# 780-00012-P4_rev3_Sch_M2_Focus_Drive.net
KiCad netlist of a schematic drawn in Altium Designer
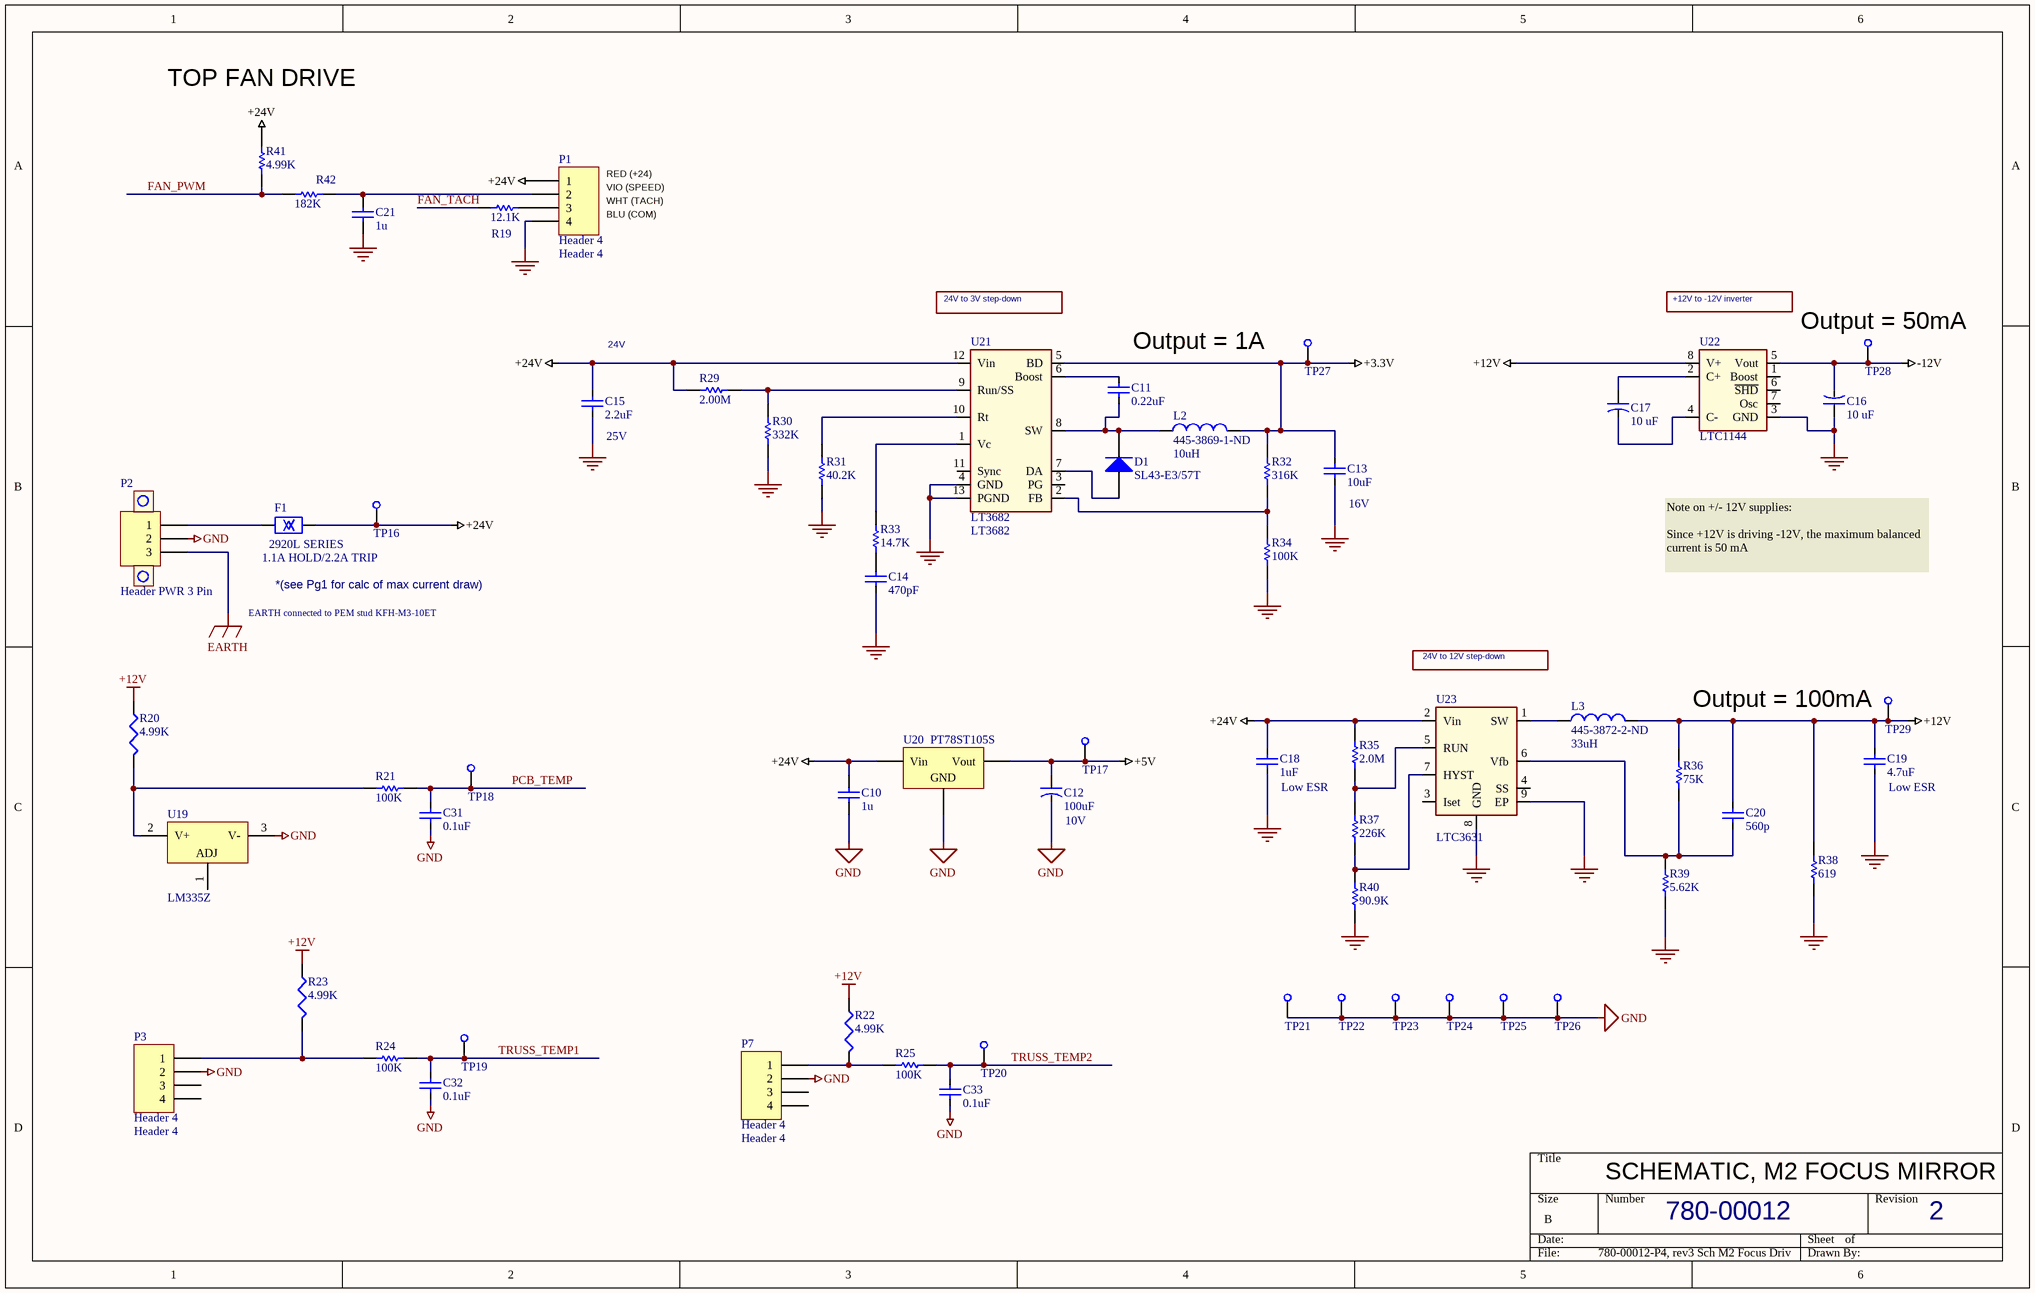
[diagram p0: 780-00012-P4, rev3 Sch M2 Focus Drive.SchDoc]

(export (version "E")
  (design (tool "Eeschema 10.0.6"))
  (components
    (comp (ref "C10")
      (value "1u")
      (footprint "2012[0805]")
      (description "Capacitor")
      (fields (field (name "MANUFACTURER") "Taiyo Yuden"))
      (libsource (lib "Miscellaneous Devices") (part "Cap"))
    )
    (comp (ref "C11")
      (value "0.22uF")
      (footprint "SMD_0805")
      (description "Capacitor")
      (fields (field (name "Comment") "Cap SMD"))
      (libsource (lib "Richs Schematic Components") (part "Cap SMD"))
    )
    (comp (ref "C12")
      (value "10V")
      (footprint "SMD_CAP_7343")
      (description "outline 6.0mm x 3.2mm")
      (fields (field (name "MANUFACTURER") "kEMET") (field (name "ALTIUM_VALUE") "100uF"))
      (libsource (lib "Richs Schematic Components") (part "Cap Tant 35V"))
    )
    (comp (ref "C13")
      (value "16V")
      (footprint "SMD_0805")
      (description "Capacitor")
      (fields (field (name "ALTIUM_VALUE") "10uF"))
      (libsource (lib "Richs Schematic Components") (part "Cap SMD"))
    )
    (comp (ref "C14")
      (value "470pF")
      (footprint "SMD_0805")
      (description "Capacitor")
      (fields (field (name "Comment") "Cap SMD"))
      (libsource (lib "Richs Schematic Components") (part "Cap SMD"))
    )
    (comp (ref "C15")
      (value "25V")
      (footprint "SMD_0805")
      (description "Capacitor")
      (fields (field (name "MANUFACTURER") "Taiyo Yuden") (field (name "ALTIUM_VALUE") "2.2uF"))
      (libsource (lib "Richs Schematic Components") (part "Cap SMD"))
    )
    (comp (ref "C16")
      (value "10 uF")
      (footprint "SMD_CAP_3216")
      (description "outline 3.2mm x 1.6mm")
      (fields (field (name "MANUFACTURER") "KEMET") (field (name "Comment") "16V"))
      (libsource (lib "Richs Schematic Components") (part "Cap Tant 16V"))
    )
    (comp (ref "C17")
      (value "10 uF")
      (footprint "SMD_CAP_3216")
      (description "outline 3.2mm x 1.6mm")
      (fields (field (name "MANUFACTURER") "KEMET") (field (name "Comment") "16V"))
      (libsource (lib "Richs Schematic Components") (part "Cap Tant 16V"))
    )
    (comp (ref "C18")
      (value "Low ESR")
      (footprint "SMD_1206")
      (description "Capacitor")
      (fields (field (name "MANUFACTURER") "TDK") (field (name "ALTIUM_VALUE") "1uF"))
      (libsource (lib "Richs Schematic Components") (part "Cap SMD"))
    )
    (comp (ref "C19")
      (value "Low ESR")
      (footprint "SMD_1206")
      (description "Capacitor")
      (fields (field (name "MANUFACTURER") "TDK") (field (name "ALTIUM_VALUE") "4.7uF"))
      (libsource (lib "Richs Schematic Components") (part "Cap SMD"))
    )
    (comp (ref "C20")
      (value "560p")
      (footprint "SMD_0805")
      (description "Capacitor")
      (fields (field (name "Comment") "Cap SMD"))
      (libsource (lib "Richs Schematic Components") (part "Cap SMD"))
    )
    (comp (ref "C21")
      (value "1u")
      (footprint "2012[0805]")
      (description "Capacitor")
      (fields (field (name "MANUFACTURER") "Taiyo Yuden"))
      (libsource (lib "Miscellaneous Devices") (part "Cap"))
    )
    (comp (ref "C31")
      (value "0.1uF")
      (footprint "SMD_0805")
      (description "Capacitor")
      (fields (field (name "MANUFACTURER") "AVX") (field (name "Comment") "Cap SMD"))
      (libsource (lib "Richs Schematic Components") (part "Cap SMD"))
    )
    (comp (ref "C32")
      (value "0.1uF")
      (footprint "SMD_0805")
      (description "Capacitor")
      (fields (field (name "MANUFACTURER") "AVX") (field (name "Comment") "Cap SMD"))
      (libsource (lib "Richs Schematic Components") (part "Cap SMD"))
    )
    (comp (ref "C33")
      (value "0.1uF")
      (footprint "SMD_0805")
      (description "Capacitor")
      (fields (field (name "MANUFACTURER") "AVX") (field (name "Comment") "Cap SMD"))
      (libsource (lib "Richs Schematic Components") (part "Cap SMD"))
    )
    (comp (ref "D1")
      (value "SL43-E3/57T")
      (footprint "DO-214AB")
      (description "Default Diode")
      (fields (field (name "MANUFACTURER") "Vishay/Dale"))
      (libsource (lib "Miscellaneous Devices") (part "Diode"))
    )
    (comp (ref "F1")
      (value "2920L SERIES")
      (footprint "SMD 2920  PolySwitch")
      (description "Polyswitch")
      (fields (field (name "ALTIUM_VALUE") "1.1A HOLD/2.2A TRIP"))
      (libsource (lib "Richs Schematic Components") (part "Fuse Resettable"))
    )
    (comp (ref "L2")
      (value "445-3869-1-ND")
      (footprint "Inductor TDC SLF")
      (description "Inductor")
      (fields (field (name "MANUFACTURER") "TDK") (field (name "ALTIUM_VALUE") "10uH"))
      (libsource (lib "Richs Schematic Components") (part "Inductor SMD 10uH 1.8A"))
    )
    (comp (ref "L3")
      (value "445-3872-2-ND")
      (footprint "Inductor TDC SLF")
      (description "Inductor")
      (fields (field (name "MANUFACTURER") "TDK") (field (name "ALTIUM_VALUE") "33uH"))
      (libsource (lib "Richs Schematic Components") (part "Inductor SMD 10uH 1.8A"))
    )
    (comp (ref "P1")
      (value "Header 4")
      (footprint "HDR1X4 for IDC")
      (description "Header, 4-Pin")
      (fields (field (name "ALTIUM_VALUE") "Header 4"))
      (libsource (lib "") (part "Header 4_1"))
    )
    (comp (ref "P2")
      (value "Header PWR 3 Pin")
      (footprint "HDR-3 pin w/screw")
      (description "Header, 3-Pin")
      (fields (field (name "MANUFACTURER") "Tyco"))
      (libsource (lib "Richs Schematic Components") (part "Header 3 PWR"))
    )
    (comp (ref "P3")
      (value "Header 4")
      (footprint "HDR1X4 for IDC")
      (description "Header, 4-Pin")
      (fields (field (name "ALTIUM_VALUE") "Header 4"))
      (libsource (lib "Richs Schematic Components") (part "Header 4"))
    )
    (comp (ref "P7")
      (value "Header 4")
      (footprint "HDR1X4 for IDC")
      (description "Header, 4-Pin")
      (fields (field (name "ALTIUM_VALUE") "Header 4"))
      (libsource (lib "Richs Schematic Components") (part "Header 4"))
    )
    (comp (ref "R19")
      (value "12.1K")
      (footprint "SMD_0805")
      (description "Resistor 0805")
      (fields (field (name "MANUFACTURER") "Vishay/Dale") (field (name "Comment") "Res 0805"))
      (libsource (lib "Richs Schematic Components") (part "Res SMD"))
    )
    (comp (ref "R20")
      (value "4.99K")
      (footprint "smd_0805")
      (description "Resistor")
      (fields (field (name "MANUFACTURER") "DALE") (field (name "Comment") "Res3"))
      (libsource (lib "Miscellaneous Devices") (part "Res3"))
    )
    (comp (ref "R21")
      (value "100K")
      (footprint "SMD_0805")
      (description "Resistor")
      (fields (field (name "MANUFACTURER") "Vishay/Dale") (field (name "Comment") "Res SMD"))
      (libsource (lib "Richs Schematic Components") (part "Res SMD"))
    )
    (comp (ref "R22")
      (value "4.99K")
      (footprint "smd_0805")
      (description "Resistor")
      (fields (field (name "MANUFACTURER") "DALE") (field (name "Comment") "Res3"))
      (libsource (lib "Miscellaneous Devices") (part "Res3"))
    )
    (comp (ref "R23")
      (value "4.99K")
      (footprint "smd_0805")
      (description "Resistor")
      (fields (field (name "MANUFACTURER") "DALE") (field (name "Comment") "Res3"))
      (libsource (lib "Miscellaneous Devices") (part "Res3"))
    )
    (comp (ref "R24")
      (value "100K")
      (footprint "SMD_0805")
      (description "Resistor")
      (fields (field (name "MANUFACTURER") "Vishay/Dale") (field (name "Comment") "Res SMD"))
      (libsource (lib "Richs Schematic Components") (part "Res SMD"))
    )
    (comp (ref "R25")
      (value "100K")
      (footprint "SMD_0805")
      (description "Resistor")
      (fields (field (name "MANUFACTURER") "Vishay/Dale") (field (name "Comment") "Res SMD"))
      (libsource (lib "Richs Schematic Components") (part "Res SMD"))
    )
    (comp (ref "R29")
      (value "2.00M")
      (footprint "SMD_0805")
      (description "Resistor 0805")
      (fields (field (name "MANUFACTURER") "Vishay/Dale") (field (name "Comment") "Res 0805"))
      (libsource (lib "Richs Schematic Components") (part "Res SMD"))
    )
    (comp (ref "R30")
      (value "332K")
      (footprint "SMD_0805")
      (description "Resistor 0805")
      (fields (field (name "MANUFACTURER") "Vishay/Dale") (field (name "Comment") "Res 0805"))
      (libsource (lib "Richs Schematic Components") (part "Res SMD"))
    )
    (comp (ref "R31")
      (value "40.2K")
      (footprint "SMD_0805")
      (description "Resistor 0805")
      (fields (field (name "MANUFACTURER") "Vishay/Dale") (field (name "Comment") "Res 0805"))
      (libsource (lib "Richs Schematic Components") (part "Res SMD"))
    )
    (comp (ref "R32")
      (value "316K")
      (footprint "SMD_0805")
      (description "Resistor 0805")
      (fields (field (name "MANUFACTURER") "Vishay/Dale") (field (name "Comment") "Res 0805"))
      (libsource (lib "Richs Schematic Components") (part "Res SMD"))
    )
    (comp (ref "R33")
      (value "14.7K")
      (footprint "SMD_0805")
      (description "Resistor 0805")
      (fields (field (name "MANUFACTURER") "Vishay/Dale") (field (name "Comment") "Res 0805"))
      (libsource (lib "Richs Schematic Components") (part "Res SMD"))
    )
    (comp (ref "R34")
      (value "100K")
      (footprint "SMD_0805")
      (description "Resistor 0805")
      (fields (field (name "MANUFACTURER") "Vishay/Dale") (field (name "Comment") "Res 0805"))
      (libsource (lib "Richs Schematic Components") (part "Res SMD"))
    )
    (comp (ref "R35")
      (value "2.0M")
      (footprint "SMD_0805")
      (description "Resistor 0805")
      (fields (field (name "MANUFACTURER") "Vishay/Dale") (field (name "Comment") "Res 0805"))
      (libsource (lib "Richs Schematic Components") (part "Res SMD"))
    )
    (comp (ref "R36")
      (value "75K")
      (footprint "SMD_0805")
      (description "Resistor 0805")
      (fields (field (name "MANUFACTURER") "Vishay/Dale") (field (name "Comment") "Res 0805"))
      (libsource (lib "Richs Schematic Components") (part "Res SMD"))
    )
    (comp (ref "R37")
      (value "226K")
      (footprint "SMD_0805")
      (description "Resistor 0805")
      (fields (field (name "MANUFACTURER") "Vishay/Dale") (field (name "Comment") "Res 0805"))
      (libsource (lib "Richs Schematic Components") (part "Res SMD"))
    )
    (comp (ref "R38")
      (value "619")
      (footprint "SMD_0805")
      (description "Resistor 0805")
      (fields (field (name "MANUFACTURER") "Vishay/Dale") (field (name "Comment") "Res 0805"))
      (libsource (lib "Richs Schematic Components") (part "Res SMD"))
    )
    (comp (ref "R39")
      (value "5.62K")
      (footprint "SMD_0805")
      (description "Resistor 0805")
      (fields (field (name "MANUFACTURER") "Vishay/Dale") (field (name "Comment") "Res 0805"))
      (libsource (lib "Richs Schematic Components") (part "Res SMD"))
    )
    (comp (ref "R40")
      (value "90.9K")
      (footprint "SMD_0805")
      (description "Resistor 0805")
      (fields (field (name "MANUFACTURER") "Vishay/Dale") (field (name "Comment") "Res 0805"))
      (libsource (lib "Richs Schematic Components") (part "Res SMD"))
    )
    (comp (ref "R41")
      (value "4.99K")
      (footprint "SMD_0805")
      (description "Resistor 0805")
      (fields (field (name "MANUFACTURER") "Vishay/Dale") (field (name "Comment") "Res 0805"))
      (libsource (lib "Richs Schematic Components") (part "Res SMD"))
    )
    (comp (ref "R42")
      (value "182K")
      (footprint "SMD_0805")
      (description "Resistor 0805")
      (fields (field (name "MANUFACTURER") "Vishay/Dale") (field (name "Comment") "Res 0805"))
      (libsource (lib "Richs Schematic Components") (part "Res SMD"))
    )
    (comp (ref "TP16")
      (value "Test Point SMD")
      (footprint "SMD_TEST POINT")
      (description "SMD loop test point")
      (libsource (lib "Richs Schematic Components") (part "Test Point SMD"))
    )
    (comp (ref "TP17")
      (value "Test Point SMD")
      (footprint "SMD_TEST POINT")
      (description "SMD loop test point")
      (libsource (lib "Richs Schematic Components") (part "Test Point SMD"))
    )
    (comp (ref "TP18")
      (value "Test Point SMD")
      (footprint "SMD_TEST POINT")
      (description "SMD loop test point")
      (libsource (lib "Richs Schematic Components") (part "Test Point SMD"))
    )
    (comp (ref "TP19")
      (value "Test Point SMD")
      (footprint "SMD_TEST POINT")
      (description "SMD loop test point")
      (libsource (lib "Richs Schematic Components") (part "Test Point SMD"))
    )
    (comp (ref "TP20")
      (value "Test Point SMD")
      (footprint "SMD_TEST POINT")
      (description "SMD loop test point")
      (libsource (lib "Richs Schematic Components") (part "Test Point SMD"))
    )
    (comp (ref "TP21")
      (value "Test Point SMD")
      (footprint "SMD_TEST POINT")
      (description "SMD loop test point")
      (libsource (lib "Richs Schematic Components") (part "Test Point SMD"))
    )
    (comp (ref "TP22")
      (value "Test Point SMD")
      (footprint "SMD_TEST POINT")
      (description "SMD loop test point")
      (libsource (lib "Richs Schematic Components") (part "Test Point SMD"))
    )
    (comp (ref "TP23")
      (value "Test Point SMD")
      (footprint "SMD_TEST POINT")
      (description "SMD loop test point")
      (libsource (lib "Richs Schematic Components") (part "Test Point SMD"))
    )
    (comp (ref "TP24")
      (value "Test Point SMD")
      (footprint "SMD_TEST POINT")
      (description "SMD loop test point")
      (libsource (lib "Richs Schematic Components") (part "Test Point SMD"))
    )
    (comp (ref "TP25")
      (value "Test Point SMD")
      (footprint "SMD_TEST POINT")
      (description "SMD loop test point")
      (libsource (lib "Richs Schematic Components") (part "Test Point SMD"))
    )
    (comp (ref "TP26")
      (value "Test Point SMD")
      (footprint "SMD_TEST POINT")
      (description "SMD loop test point")
      (libsource (lib "Richs Schematic Components") (part "Test Point SMD"))
    )
    (comp (ref "TP27")
      (value "Test Point SMD")
      (footprint "SMD_TEST POINT")
      (description "SMD loop test point")
      (libsource (lib "Richs Schematic Components") (part "Test Point SMD"))
    )
    (comp (ref "TP28")
      (value "Test Point SMD")
      (footprint "SMD_TEST POINT")
      (description "SMD loop test point")
      (libsource (lib "Richs Schematic Components") (part "Test Point SMD"))
    )
    (comp (ref "TP29")
      (value "Test Point SMD")
      (footprint "SMD_TEST POINT")
      (description "SMD loop test point")
      (libsource (lib "Richs Schematic Components") (part "Test Point SMD"))
    )
    (comp (ref "U19")
      (value "LM335Z")
      (footprint "Z03A")
      (description "Precision Temperature Sensor")
      (fields (field (name "MANUFACTURER") "National Semiconductor"))
      (libsource (lib "NSC Temperature Sensor") (part "LM335Z"))
    )
    (comp (ref "U20")
      (value "PT78ST105S")
      (footprint "PSIP_3_SMD")
      (description "Voltage Regulator")
      (fields (field (name "MANUFACTURER") "Texas Instruments"))
      (libsource (lib "Miscellaneous Devices") (part "Volt Reg"))
    )
    (comp (ref "U21")
      (value "LT3682")
      (footprint "DD12/DFN12")
      (description "1A uPwr Step-Down switching regulator")
      (fields (field (name "MANUFACTURER") "Linear") (field (name "ALTIUM_VALUE") "LT3682"))
      (libsource (lib "Richs Schematic Components") (part "LT3682"))
    )
    (comp (ref "U22")
      (value "LTC1144")
      (footprint "S8_M")
      (description "IC VOLT CONV SW-CAP W/SHTDN8SOIC")
      (fields (field (name "MANUFACTURER") "Linear"))
      (libsource (lib "Richs Schematic Components") (part "LTC1144"))
    )
    (comp (ref "U23")
      (value "LTC3631")
      (footprint "DD8/DFN8")
      (description "IC CONV STP-DWN ADJ 8-DFN")
      (fields (field (name "MANUFACTURER") "Linear"))
      (libsource (lib "Richs Schematic Components") (part "LTC3631"))
    )
  )
  (nets
    (net (code "1") (name "+3.3V") (class "Default")
      (node (ref "C13") (pin "2") (pinfunction "2_2") (pintype "passive"))
      (node (ref "L2") (pin "2") (pinfunction "2_2") (pintype "passive"))
      (node (ref "R32") (pin "2") (pinfunction "2_2") (pintype "passive"))
      (node (ref "TP27") (pin "1") (pinfunction "TP_1") (pintype "passive"))
      (node (ref "U21") (pin "5") (pinfunction "BD_5") (pintype "passive"))
    )
    (net (code "2") (name "+5V") (class "Default")
      (node (ref "C12") (pin "pos") (pinfunction "1_pos") (pintype "passive"))
      (node (ref "TP17") (pin "1") (pinfunction "TP_1") (pintype "passive"))
      (node (ref "U20") (pin "3") (pinfunction "Vout_3") (pintype "passive"))
    )
    (net (code "3") (name "+12V") (class "Default")
      (node (ref "C19") (pin "2") (pinfunction "2_2") (pintype "passive"))
      (node (ref "C20") (pin "2") (pinfunction "2_2") (pintype "passive"))
      (node (ref "L3") (pin "2") (pinfunction "2_2") (pintype "passive"))
      (node (ref "R20") (pin "1") (pinfunction "1_1") (pintype "passive"))
      (node (ref "R22") (pin "1") (pinfunction "1_1") (pintype "passive"))
      (node (ref "R23") (pin "1") (pinfunction "1_1") (pintype "passive"))
      (node (ref "R36") (pin "2") (pinfunction "2_2") (pintype "passive"))
      (node (ref "R38") (pin "2") (pinfunction "2_2") (pintype "passive"))
      (node (ref "TP29") (pin "1") (pinfunction "TP_1") (pintype "passive"))
      (node (ref "U22") (pin "8") (pinfunction "V+_8") (pintype "power_in"))
    )
    (net (code "4") (name "+24V") (class "Default")
      (node (ref "C10") (pin "1") (pinfunction "1_1") (pintype "passive"))
      (node (ref "C15") (pin "2") (pinfunction "2_2") (pintype "passive"))
      (node (ref "C18") (pin "2") (pinfunction "2_2") (pintype "passive"))
      (node (ref "F1") (pin "2") (pinfunction "2_2") (pintype "passive"))
      (node (ref "P1") (pin "1") (pinfunction "1_1") (pintype "passive"))
      (node (ref "R29") (pin "1") (pinfunction "1_1") (pintype "passive"))
      (node (ref "R35") (pin "2") (pinfunction "2_2") (pintype "passive"))
      (node (ref "R41") (pin "2") (pinfunction "2_2") (pintype "passive"))
      (node (ref "TP16") (pin "1") (pinfunction "TP_1") (pintype "passive"))
      (node (ref "U20") (pin "1") (pinfunction "Vin_1") (pintype "passive"))
      (node (ref "U21") (pin "12") (pinfunction "Vin_12") (pintype "passive"))
      (node (ref "U23") (pin "2") (pinfunction "Vin_2") (pintype "passive"))
    )
    (net (code "5") (name "-12V") (class "Default")
      (node (ref "C16") (pin "2") (pinfunction "2_2") (pintype "passive"))
      (node (ref "TP28") (pin "1") (pinfunction "TP_1") (pintype "passive"))
      (node (ref "U22") (pin "5") (pinfunction "Vout_5") (pintype "passive"))
    )
    (net (code "6") (name "/FAN_PWM") (class "Default")
      (node (ref "R41") (pin "1") (pinfunction "1_1") (pintype "passive"))
      (node (ref "R42") (pin "1") (pinfunction "1_1") (pintype "passive"))
    )
    (net (code "7") (name "/FAN_TACH") (class "Default")
      (node (ref "R19") (pin "1") (pinfunction "1_1") (pintype "passive"))
    )
    (net (code "8") (name "/PCB_TEMP") (class "Default")
      (node (ref "C31") (pin "2") (pinfunction "2_2") (pintype "passive"))
      (node (ref "R21") (pin "1") (pinfunction "1_1") (pintype "passive"))
      (node (ref "TP18") (pin "1") (pinfunction "TP_1") (pintype "passive"))
    )
    (net (code "9") (name "/TRUSS_TEMP1") (class "Default")
      (node (ref "C32") (pin "2") (pinfunction "2_2") (pintype "passive"))
      (node (ref "R24") (pin "1") (pinfunction "1_1") (pintype "passive"))
      (node (ref "TP19") (pin "1") (pinfunction "TP_1") (pintype "passive"))
    )
    (net (code "10") (name "/TRUSS_TEMP2") (class "Default")
      (node (ref "C33") (pin "2") (pinfunction "2_2") (pintype "passive"))
      (node (ref "R25") (pin "1") (pinfunction "1_1") (pintype "passive"))
      (node (ref "TP20") (pin "1") (pinfunction "TP_1") (pintype "passive"))
    )
    (net (code "11") (name "EARTH") (class "Default")
      (node (ref "P2") (pin "3") (pinfunction "3_3") (pintype "passive"))
    )
    (net (code "12") (name "GND") (class "Default")
      (node (ref "C10") (pin "2") (pinfunction "2_2") (pintype "passive"))
      (node (ref "C12") (pin "neg") (pinfunction "2_neg") (pintype "passive"))
      (node (ref "C13") (pin "1") (pinfunction "1_1") (pintype "passive"))
      (node (ref "C14") (pin "1") (pinfunction "1_1") (pintype "passive"))
      (node (ref "C15") (pin "1") (pinfunction "1_1") (pintype "passive"))
      (node (ref "C16") (pin "1") (pinfunction "1_1") (pintype "passive"))
      (node (ref "C18") (pin "1") (pinfunction "1_1") (pintype "passive"))
      (node (ref "C19") (pin "1") (pinfunction "1_1") (pintype "passive"))
      (node (ref "C21") (pin "2") (pinfunction "2_2") (pintype "passive"))
      (node (ref "C31") (pin "1") (pinfunction "1_1") (pintype "passive"))
      (node (ref "C32") (pin "1") (pinfunction "1_1") (pintype "passive"))
      (node (ref "C33") (pin "1") (pinfunction "1_1") (pintype "passive"))
      (node (ref "P1") (pin "4") (pinfunction "4_4") (pintype "passive"))
      (node (ref "P2") (pin "2") (pinfunction "2_2") (pintype "passive"))
      (node (ref "P3") (pin "2") (pinfunction "2_2") (pintype "passive"))
      (node (ref "P7") (pin "2") (pinfunction "2_2") (pintype "passive"))
      (node (ref "R30") (pin "1") (pinfunction "1_1") (pintype "passive"))
      (node (ref "R31") (pin "1") (pinfunction "1_1") (pintype "passive"))
      (node (ref "R34") (pin "1") (pinfunction "1_1") (pintype "passive"))
      (node (ref "R38") (pin "1") (pinfunction "1_1") (pintype "passive"))
      (node (ref "R39") (pin "1") (pinfunction "1_1") (pintype "passive"))
      (node (ref "R40") (pin "1") (pinfunction "1_1") (pintype "passive"))
      (node (ref "TP21") (pin "1") (pinfunction "TP_1") (pintype "passive"))
      (node (ref "TP22") (pin "1") (pinfunction "TP_1") (pintype "passive"))
      (node (ref "TP23") (pin "1") (pinfunction "TP_1") (pintype "passive"))
      (node (ref "TP24") (pin "1") (pinfunction "TP_1") (pintype "passive"))
      (node (ref "TP25") (pin "1") (pinfunction "TP_1") (pintype "passive"))
      (node (ref "TP26") (pin "1") (pinfunction "TP_1") (pintype "passive"))
      (node (ref "U19") (pin "3") (pinfunction "V-_3") (pintype "passive"))
      (node (ref "U20") (pin "2") (pinfunction "GND_2") (pintype "passive"))
      (node (ref "U21") (pin "13") (pinfunction "PGND_13") (pintype "passive"))
      (node (ref "U21") (pin "4") (pinfunction "GND_4") (pintype "power_in"))
      (node (ref "U22") (pin "3") (pinfunction "GND_3") (pintype "passive"))
      (node (ref "U23") (pin "8") (pinfunction "GND_8") (pintype "passive"))
      (node (ref "U23") (pin "9") (pinfunction "EP_9") (pintype "passive"))
    )
    (net (code "13") (name "Net-(C14-Pad2)") (class "Default")
      (node (ref "C14") (pin "2") (pinfunction "2_2") (pintype "passive"))
      (node (ref "R33") (pin "1") (pinfunction "1_1") (pintype "passive"))
    )
    (net (code "14") (name "Net-(C21-Pad1)") (class "Default")
      (node (ref "C21") (pin "1") (pinfunction "1_1") (pintype "passive"))
      (node (ref "P1") (pin "2") (pinfunction "2_2") (pintype "passive"))
      (node (ref "R42") (pin "2") (pinfunction "2_2") (pintype "passive"))
    )
    (net (code "15") (name "Net-(D1-A)") (class "Default")
      (node (ref "D1") (pin "1") (pinfunction "A_1") (pintype "passive"))
      (node (ref "U21") (pin "7") (pinfunction "DA_7") (pintype "passive"))
    )
    (net (code "16") (name "Net-(D1-K)") (class "Default")
      (node (ref "C11") (pin "1") (pinfunction "1_1") (pintype "passive"))
      (node (ref "D1") (pin "2") (pinfunction "K_2") (pintype "passive"))
      (node (ref "L2") (pin "1") (pinfunction "1_1") (pintype "passive"))
      (node (ref "U21") (pin "8") (pinfunction "SW_8") (pintype "passive"))
    )
    (net (code "17") (name "Net-(F1-Pad1)") (class "Default")
      (node (ref "F1") (pin "1") (pinfunction "1_1") (pintype "passive"))
      (node (ref "P2") (pin "1") (pinfunction "1_1") (pintype "passive"))
    )
    (net (code "18") (name "Net-(P1-Pad3)") (class "Default")
      (node (ref "P1") (pin "3") (pinfunction "3_3") (pintype "passive"))
      (node (ref "R19") (pin "2") (pinfunction "2_2") (pintype "passive"))
    )
    (net (code "19") (name "Net-(P3-Pad1)") (class "Default")
      (node (ref "P3") (pin "1") (pinfunction "1_1") (pintype "passive"))
      (node (ref "R23") (pin "2") (pinfunction "2_2") (pintype "passive"))
      (node (ref "R24") (pin "2") (pinfunction "2_2") (pintype "passive"))
    )
    (net (code "20") (name "Net-(P7-Pad1)") (class "Default")
      (node (ref "P7") (pin "1") (pinfunction "1_1") (pintype "passive"))
      (node (ref "R22") (pin "2") (pinfunction "2_2") (pintype "passive"))
      (node (ref "R25") (pin "2") (pinfunction "2_2") (pintype "passive"))
    )
    (net (code "21") (name "Net-(U19-V+)") (class "Default")
      (node (ref "R20") (pin "2") (pinfunction "2_2") (pintype "passive"))
      (node (ref "R21") (pin "2") (pinfunction "2_2") (pintype "passive"))
      (node (ref "U19") (pin "2") (pinfunction "V+_2") (pintype "passive"))
    )
    (net (code "22") (name "Net-(U21-Boost)") (class "Default")
      (node (ref "C11") (pin "2") (pinfunction "2_2") (pintype "passive"))
      (node (ref "U21") (pin "6") (pinfunction "Boost_6") (pintype "passive"))
    )
    (net (code "23") (name "Net-(U21-FB)") (class "Default")
      (node (ref "R32") (pin "1") (pinfunction "1_1") (pintype "passive"))
      (node (ref "R34") (pin "2") (pinfunction "2_2") (pintype "passive"))
      (node (ref "U21") (pin "2") (pinfunction "FB_2") (pintype "passive"))
    )
    (net (code "24") (name "Net-(U21-Rt)") (class "Default")
      (node (ref "R31") (pin "2") (pinfunction "2_2") (pintype "passive"))
      (node (ref "U21") (pin "10") (pinfunction "Rt_10") (pintype "passive"))
    )
    (net (code "25") (name "Net-(U21-Run{slash}SS)") (class "Default")
      (node (ref "R29") (pin "2") (pinfunction "2_2") (pintype "passive"))
      (node (ref "R30") (pin "2") (pinfunction "2_2") (pintype "passive"))
      (node (ref "U21") (pin "9") (pinfunction "Run/SS_9") (pintype "passive"))
    )
    (net (code "26") (name "Net-(U21-Vc)") (class "Default")
      (node (ref "R33") (pin "2") (pinfunction "2_2") (pintype "passive"))
      (node (ref "U21") (pin "1") (pinfunction "Vc_1") (pintype "passive"))
    )
    (net (code "27") (name "Net-(U22-C+)") (class "Default")
      (node (ref "C17") (pin "1") (pinfunction "1_1") (pintype "passive"))
      (node (ref "U22") (pin "2") (pinfunction "C+_2") (pintype "passive"))
    )
    (net (code "28") (name "Net-(U22-C-)") (class "Default")
      (node (ref "C17") (pin "2") (pinfunction "2_2") (pintype "passive"))
      (node (ref "U22") (pin "4") (pinfunction "C-_4") (pintype "passive"))
    )
    (net (code "29") (name "Net-(U23-HYST)") (class "Default")
      (node (ref "R37") (pin "1") (pinfunction "1_1") (pintype "passive"))
      (node (ref "R40") (pin "2") (pinfunction "2_2") (pintype "passive"))
      (node (ref "U23") (pin "7") (pinfunction "HYST_7") (pintype "passive"))
    )
    (net (code "30") (name "Net-(U23-RUN)") (class "Default")
      (node (ref "R35") (pin "1") (pinfunction "1_1") (pintype "passive"))
      (node (ref "R37") (pin "2") (pinfunction "2_2") (pintype "passive"))
      (node (ref "U23") (pin "5") (pinfunction "RUN_5") (pintype "passive"))
    )
    (net (code "31") (name "Net-(U23-SW)") (class "Default")
      (node (ref "L3") (pin "1") (pinfunction "1_1") (pintype "passive"))
      (node (ref "U23") (pin "1") (pinfunction "SW_1") (pintype "passive"))
    )
    (net (code "32") (name "Net-(U23-Vfb)") (class "Default")
      (node (ref "C20") (pin "1") (pinfunction "1_1") (pintype "passive"))
      (node (ref "R36") (pin "1") (pinfunction "1_1") (pintype "passive"))
      (node (ref "R39") (pin "2") (pinfunction "2_2") (pintype "passive"))
      (node (ref "U23") (pin "6") (pinfunction "Vfb_6") (pintype "passive"))
    )
    (net (code "33") (name "SUPPORT") (class "Default")
      (node (ref "U20") (pin "0") (pinfunction "SUPPORT_0") (pintype "passive"))
    )
    (net (code "34") (name "unconnected-(P3-Pad3)") (class "Default")
      (node (ref "P3") (pin "3") (pinfunction "3_3") (pintype "passive"))
    )
    (net (code "35") (name "unconnected-(P3-Pad4)") (class "Default")
      (node (ref "P3") (pin "4") (pinfunction "4_4") (pintype "passive"))
    )
    (net (code "36") (name "unconnected-(P7-Pad3)") (class "Default")
      (node (ref "P7") (pin "3") (pinfunction "3_3") (pintype "passive"))
    )
    (net (code "37") (name "unconnected-(P7-Pad4)") (class "Default")
      (node (ref "P7") (pin "4") (pinfunction "4_4") (pintype "passive"))
    )
    (net (code "38") (name "unconnected-(U19-ADJ-Pad1)") (class "Default")
      (node (ref "U19") (pin "1") (pinfunction "ADJ_1") (pintype "passive"))
    )
    (net (code "39") (name "unconnected-(U21-PG-Pad3)") (class "Default")
      (node (ref "U21") (pin "3") (pinfunction "PG_3") (pintype "passive"))
    )
    (net (code "40") (name "unconnected-(U21-Sync-Pad11)") (class "Default")
      (node (ref "U21") (pin "11") (pinfunction "Sync_11") (pintype "passive"))
    )
    (net (code "41") (name "unconnected-(U22-Boost-Pad1)") (class "Default")
      (node (ref "U22") (pin "1") (pinfunction "Boost_1") (pintype "passive"))
    )
    (net (code "42") (name "unconnected-(U22-Osc-Pad7)") (class "Default")
      (node (ref "U22") (pin "7") (pinfunction "Osc_7") (pintype "passive"))
    )
    (net (code "43") (name "unconnected-(U22-~{SHD}-Pad6)") (class "Default")
      (node (ref "U22") (pin "6") (pinfunction "~{SHD}_6") (pintype "passive"))
    )
    (net (code "44") (name "unconnected-(U23-Iset-Pad3)") (class "Default")
      (node (ref "U23") (pin "3") (pinfunction "Iset_3") (pintype "passive"))
    )
    (net (code "45") (name "unconnected-(U23-SS-Pad4)") (class "Default")
      (node (ref "U23") (pin "4") (pinfunction "SS_4") (pintype "passive"))
    )
  )
)
